# JediLightSwitch.net
KiCad netlist of a schematic drawn in EAGLE
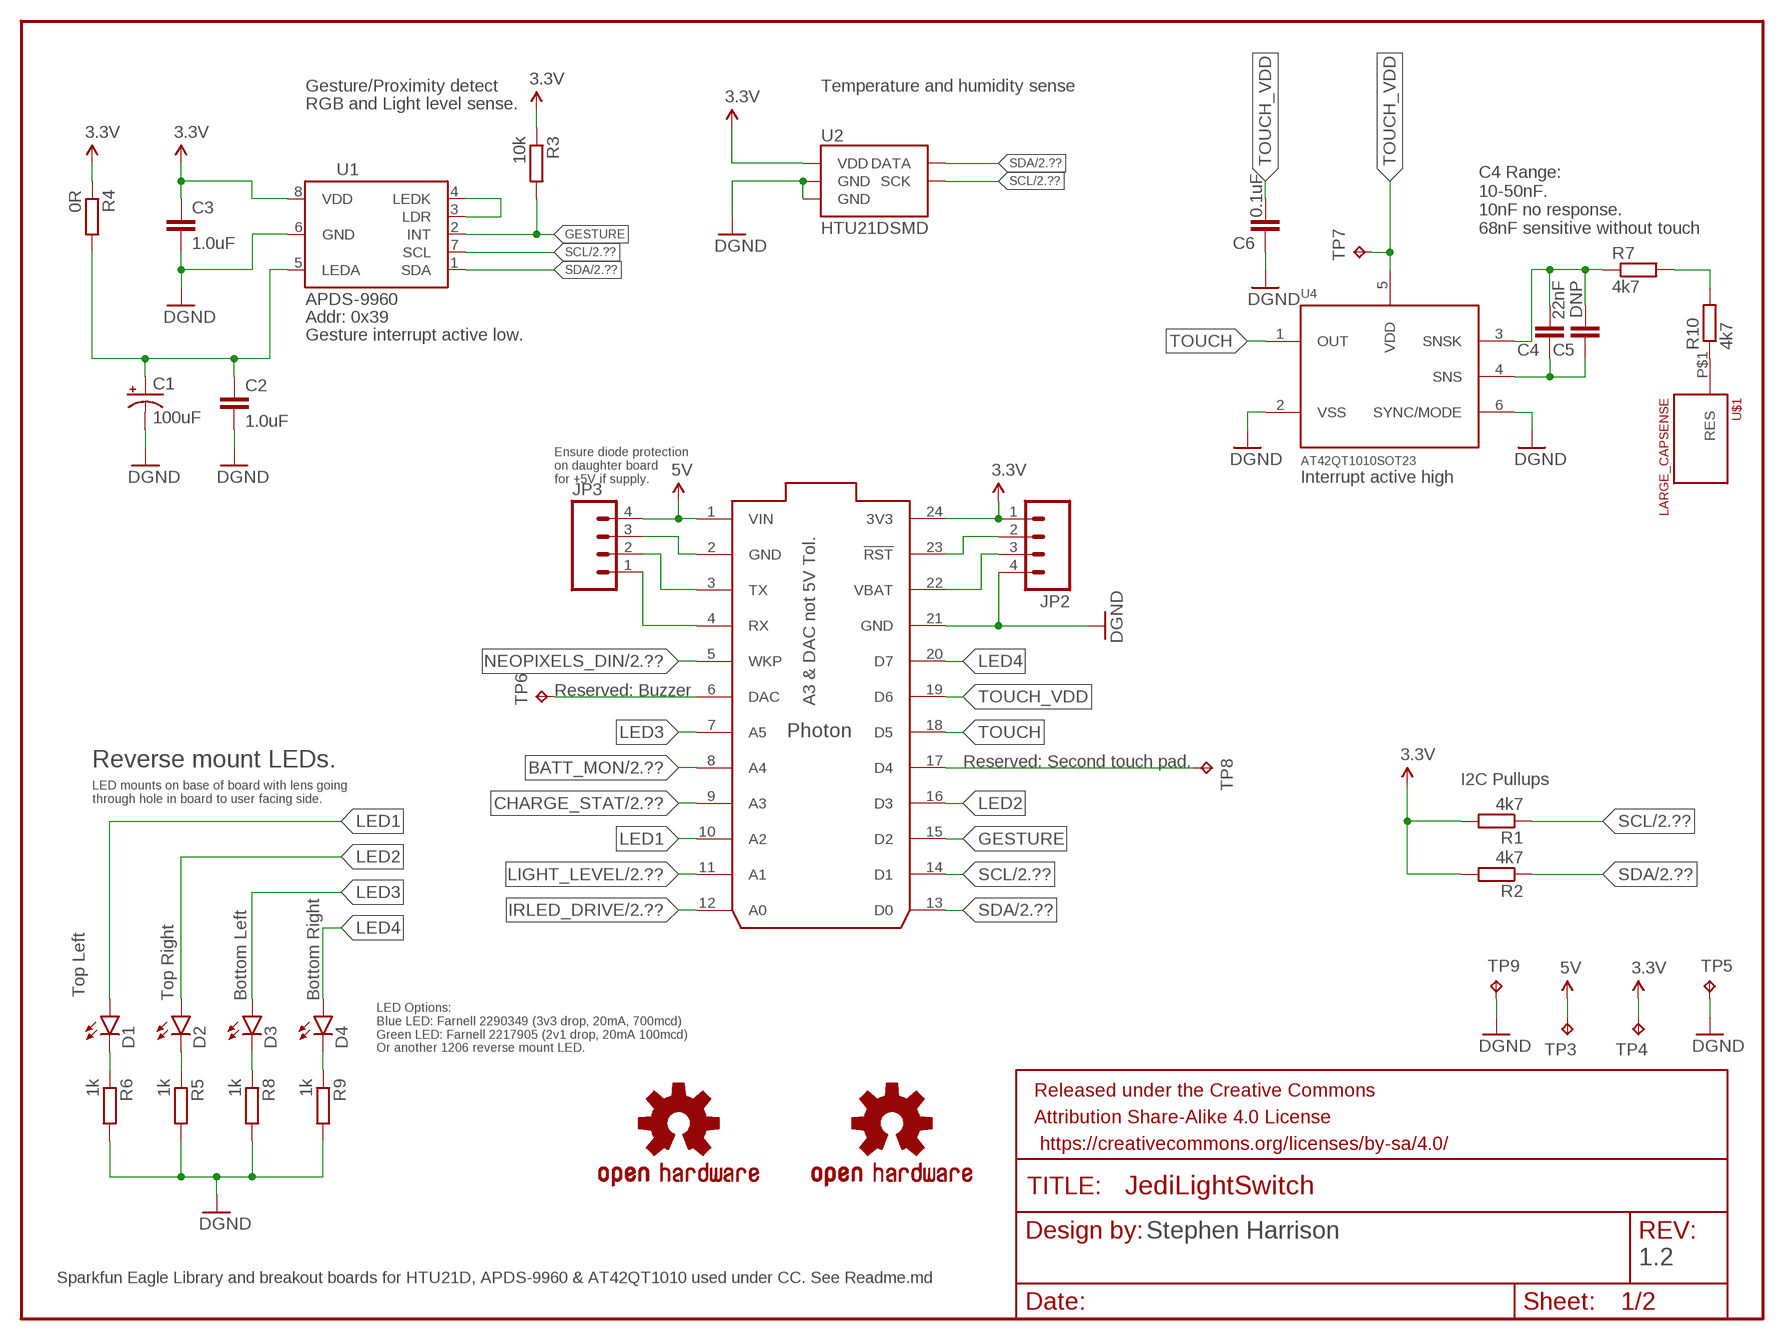
[diagram p0: schematic, sheet 1]
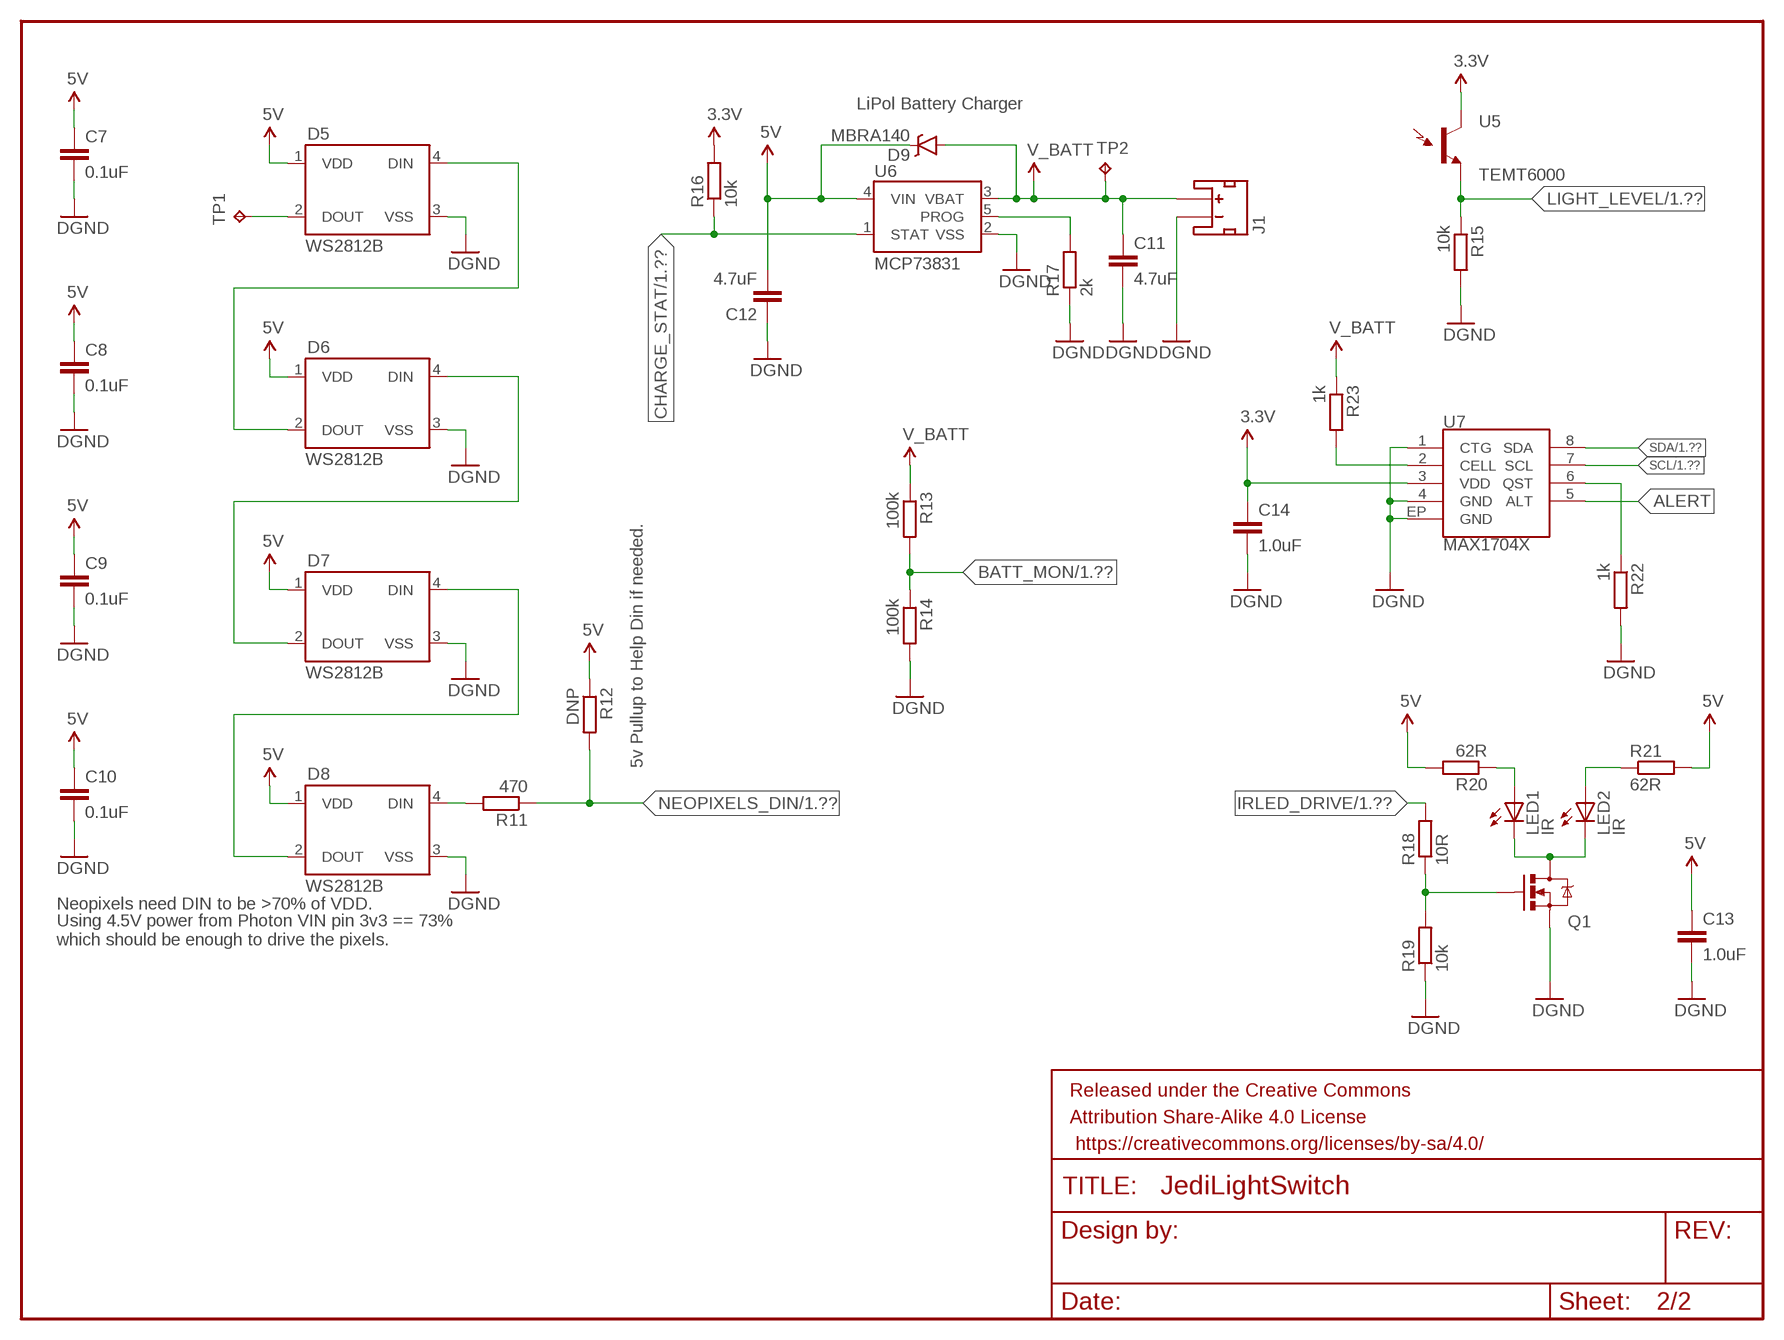
[diagram p1: schematic, sheet 2]

(export (version "E")
  (design (tool "Eeschema 10.0.6"))
  (components
    (comp (ref "C1")
      (value "100uF")
      (footprint "eagle-import:EIA7343")
      (libsource (lib "eagle-import") (part "100UF-10V-10%(TANT)"))
    )
    (comp (ref "C2")
      (value "1.0uF")
      (footprint "eagle-import:C0805")
      (libsource (lib "eagle-import") (part "C-EUC0805"))
    )
    (comp (ref "C3")
      (value "1.0uF")
      (footprint "eagle-import:C0805")
      (libsource (lib "eagle-import") (part "C-EUC0805"))
    )
    (comp (ref "C4")
      (value "22nF")
      (footprint "eagle-import:C0805")
      (libsource (lib "eagle-import") (part "C-EUC0805"))
    )
    (comp (ref "C5")
      (value "DNP")
      (footprint "eagle-import:C0805")
      (libsource (lib "eagle-import") (part "C-EUC0805"))
    )
    (comp (ref "C6")
      (value "0.1uF")
      (footprint "eagle-import:C0805")
      (libsource (lib "eagle-import") (part "C-EUC0805"))
    )
    (comp (ref "D1")
      (value "LED1206-BOTTOM")
      (footprint "eagle-import:LED-1206-BOTTOM")
      (libsource (lib "eagle-import") (part "LED1206-BOTTOM"))
    )
    (comp (ref "D2")
      (value "LED1206-BOTTOM")
      (footprint "eagle-import:LED-1206-BOTTOM")
      (libsource (lib "eagle-import") (part "LED1206-BOTTOM"))
    )
    (comp (ref "D3")
      (value "LED1206-BOTTOM")
      (footprint "eagle-import:LED-1206-BOTTOM")
      (libsource (lib "eagle-import") (part "LED1206-BOTTOM"))
    )
    (comp (ref "D4")
      (value "LED1206-BOTTOM")
      (footprint "eagle-import:LED-1206-BOTTOM")
      (libsource (lib "eagle-import") (part "LED1206-BOTTOM"))
    )
    (comp (ref "FRAME2")
      (value "FRAME-LETTER")
      (footprint "eagle-import:CREATIVE_COMMONS")
      (libsource (lib "eagle-import") (part "FRAME-LETTER"))
    )
    (comp (ref "JP2")
      (value "M04SMD_STRAIGHT_COMBO")
      (footprint "eagle-import:1X04_SMD_STRAIGHT_COMBO")
      (libsource (lib "eagle-import") (part "M04SMD_STRAIGHT_COMBO"))
    )
    (comp (ref "JP3")
      (value "M04SMD_STRAIGHT_COMBO")
      (footprint "eagle-import:1X04_SMD_STRAIGHT_COMBO")
      (libsource (lib "eagle-import") (part "M04SMD_STRAIGHT_COMBO"))
    )
    (comp (ref "LOGO1")
      (value "OSHW-LOGOM")
      (footprint "eagle-import:OSHW-LOGO-M")
      (libsource (lib "eagle-import") (part "OSHW-LOGOM"))
    )
    (comp (ref "LOGO2")
      (value "OSHW-LOGOM")
      (footprint "eagle-import:OSHW-LOGO-M")
      (libsource (lib "eagle-import") (part "OSHW-LOGOM"))
    )
    (comp (ref "R1")
      (value "4k7")
      (footprint "eagle-import:R0805")
      (libsource (lib "eagle-import") (part "R-EU_R0805"))
    )
    (comp (ref "R2")
      (value "4k7")
      (footprint "eagle-import:R0805")
      (libsource (lib "eagle-import") (part "R-EU_R0805"))
    )
    (comp (ref "R3")
      (value "10k")
      (footprint "eagle-import:R0805")
      (libsource (lib "eagle-import") (part "R-EU_R0805"))
    )
    (comp (ref "R4")
      (value "0R")
      (footprint "eagle-import:R0805")
      (libsource (lib "eagle-import") (part "R-EU_R0805"))
    )
    (comp (ref "R5")
      (value "1k")
      (footprint "eagle-import:R0805")
      (libsource (lib "eagle-import") (part "R-EU_R0805"))
    )
    (comp (ref "R6")
      (value "1k")
      (footprint "eagle-import:R0805")
      (libsource (lib "eagle-import") (part "R-EU_R0805"))
    )
    (comp (ref "R7")
      (value "4k7")
      (footprint "eagle-import:R0805")
      (libsource (lib "eagle-import") (part "R-EU_R0805"))
    )
    (comp (ref "R8")
      (value "1k")
      (footprint "eagle-import:R0805")
      (libsource (lib "eagle-import") (part "R-EU_R0805"))
    )
    (comp (ref "R9")
      (value "1k")
      (footprint "eagle-import:R0805")
      (libsource (lib "eagle-import") (part "R-EU_R0805"))
    )
    (comp (ref "R10")
      (value "4k7")
      (footprint "eagle-import:R0805")
      (libsource (lib "eagle-import") (part "R-EU_R0805"))
    )
    (comp (ref "TP3")
      (value "TPTP20R")
      (footprint "eagle-import:TP20R")
      (libsource (lib "eagle-import") (part "TPTP20R"))
    )
    (comp (ref "TP4")
      (value "3v3")
      (footprint "eagle-import:TP20R")
      (libsource (lib "eagle-import") (part "TPTP20R"))
    )
    (comp (ref "TP5")
      (value "TPTP20R")
      (footprint "eagle-import:TP20R")
      (libsource (lib "eagle-import") (part "TPTP20R"))
    )
    (comp (ref "TP6")
      (value "TPTP20R")
      (footprint "eagle-import:TP20R")
      (libsource (lib "eagle-import") (part "TPTP20R"))
    )
    (comp (ref "TP7")
      (value "TPTP20R")
      (footprint "eagle-import:TP20R")
      (libsource (lib "eagle-import") (part "TPTP20R"))
    )
    (comp (ref "TP8")
      (value "TPTP20R")
      (footprint "eagle-import:TP20R")
      (libsource (lib "eagle-import") (part "TPTP20R"))
    )
    (comp (ref "TP9")
      (value "TPTP20R")
      (footprint "eagle-import:TP20R")
      (libsource (lib "eagle-import") (part "TPTP20R"))
    )
    (comp (ref "U$1")
      (value "LARGE_CAPSENSE")
      (footprint "eagle-import:LARGE_CAPSENSE")
      (libsource (lib "eagle-import") (part "LARGE_CAPSENSE"))
    )
    (comp (ref "U1")
      (value "APDS-9960")
      (footprint "eagle-import:APDS-9960")
      (libsource (lib "eagle-import") (part "APDS-9960"))
    )
    (comp (ref "U2")
      (value "HTU21DSMD")
      (footprint "eagle-import:HTU21D")
      (libsource (lib "eagle-import") (part "HTU21DSMD"))
    )
    (comp (ref "U3")
      (value "PHOTON_SMD")
      (footprint "eagle-import:PHOTON_SMD")
      (libsource (lib "eagle-import") (part "PHOTON_SMD"))
    )
    (comp (ref "U4")
      (value "AT42QT1010SOT23")
      (footprint "eagle-import:SOT23-6")
      (libsource (lib "eagle-import") (part "AT42QT1010SOT23"))
    )
    (comp (ref "C7")
      (value "0.1uF")
      (footprint "eagle-import:C0805")
      (libsource (lib "eagle-import") (part "C-EUC0805"))
    )
    (comp (ref "C8")
      (value "0.1uF")
      (footprint "eagle-import:C0805")
      (libsource (lib "eagle-import") (part "C-EUC0805"))
    )
    (comp (ref "C9")
      (value "0.1uF")
      (footprint "eagle-import:C0805")
      (libsource (lib "eagle-import") (part "C-EUC0805"))
    )
    (comp (ref "C10")
      (value "0.1uF")
      (footprint "eagle-import:C0805")
      (libsource (lib "eagle-import") (part "C-EUC0805"))
    )
    (comp (ref "C11")
      (value "4.7uF")
      (footprint "eagle-import:C0805")
      (libsource (lib "eagle-import") (part "C-EUC0805"))
    )
    (comp (ref "C12")
      (value "4.7uF")
      (footprint "eagle-import:C0805")
      (libsource (lib "eagle-import") (part "C-EUC0805"))
    )
    (comp (ref "C13")
      (value "1.0uF")
      (footprint "eagle-import:C0805")
      (libsource (lib "eagle-import") (part "C-EUC0805"))
    )
    (comp (ref "C14")
      (value "1.0uF")
      (footprint "eagle-import:C0805")
      (libsource (lib "eagle-import") (part "C-EUC0805"))
    )
    (comp (ref "D5")
      (value "WS2812B")
      (footprint "eagle-import:WS2812B")
      (libsource (lib "eagle-import") (part "WS2812B"))
    )
    (comp (ref "D6")
      (value "WS2812B")
      (footprint "eagle-import:WS2812B")
      (libsource (lib "eagle-import") (part "WS2812B"))
    )
    (comp (ref "D7")
      (value "WS2812B")
      (footprint "eagle-import:WS2812B")
      (libsource (lib "eagle-import") (part "WS2812B"))
    )
    (comp (ref "D8")
      (value "WS2812B")
      (footprint "eagle-import:WS2812B")
      (libsource (lib "eagle-import") (part "WS2812B"))
    )
    (comp (ref "D9")
      (value "MBRA140")
      (footprint "eagle-import:SMA-DIODE")
      (libsource (lib "eagle-import") (part "MBRA140"))
    )
    (comp (ref "FRAME1")
      (value "FRAME-LETTERNO_PACKAGE")
      (footprint "eagle-import:DUMMY")
      (fields (field (name "DESIGNER") "Nobody"))
      (libsource (lib "eagle-import") (part "FRAME-LETTERNO_PACKAGE"))
    )
    (comp (ref "J1")
      (value "JST_2MM_MALE")
      (footprint "eagle-import:JST-2-SMD")
      (libsource (lib "eagle-import") (part "JST_2MM_MALE"))
    )
    (comp (ref "LED1")
      (value "IR")
      (footprint "eagle-import:1206")
      (libsource (lib "eagle-import") (part "LEDSMT1206"))
    )
    (comp (ref "LED2")
      (value "IR")
      (footprint "eagle-import:1206")
      (libsource (lib "eagle-import") (part "LEDSMT1206"))
    )
    (comp (ref "Q1")
      (value "MOSFET-NCHANNELAO3404A")
      (footprint "eagle-import:SOT23-3")
      (libsource (lib "eagle-import") (part "MOSFET-NCHANNELAO3404A"))
    )
    (comp (ref "R11")
      (value "470")
      (footprint "eagle-import:R0805")
      (libsource (lib "eagle-import") (part "R-EU_R0805"))
    )
    (comp (ref "R12")
      (value "DNP")
      (footprint "eagle-import:R0805")
      (libsource (lib "eagle-import") (part "R-EU_R0805"))
    )
    (comp (ref "R13")
      (value "100k")
      (footprint "eagle-import:R0805")
      (libsource (lib "eagle-import") (part "R-EU_R0805"))
    )
    (comp (ref "R14")
      (value "100k")
      (footprint "eagle-import:R0805")
      (libsource (lib "eagle-import") (part "R-EU_R0805"))
    )
    (comp (ref "R15")
      (value "10k")
      (footprint "eagle-import:R0805")
      (libsource (lib "eagle-import") (part "R-EU_R0805"))
    )
    (comp (ref "R16")
      (value "10k")
      (footprint "eagle-import:R0805")
      (libsource (lib "eagle-import") (part "R-EU_R0805"))
    )
    (comp (ref "R17")
      (value "2k")
      (footprint "eagle-import:R0805")
      (libsource (lib "eagle-import") (part "R-EU_R0805"))
    )
    (comp (ref "R18")
      (value "10R")
      (footprint "eagle-import:R0805")
      (libsource (lib "eagle-import") (part "R-EU_R0805"))
    )
    (comp (ref "R19")
      (value "10k")
      (footprint "eagle-import:R0805")
      (libsource (lib "eagle-import") (part "R-EU_R0805"))
    )
    (comp (ref "R20")
      (value "62R")
      (footprint "eagle-import:R0805")
      (libsource (lib "eagle-import") (part "R-EU_R0805"))
    )
    (comp (ref "R21")
      (value "62R")
      (footprint "eagle-import:R0805")
      (libsource (lib "eagle-import") (part "R-EU_R0805"))
    )
    (comp (ref "R22")
      (value "1k")
      (footprint "eagle-import:R0805")
      (libsource (lib "eagle-import") (part "R-EU_R0805"))
    )
    (comp (ref "R23")
      (value "1k")
      (footprint "eagle-import:R0805")
      (libsource (lib "eagle-import") (part "R-EU_R0805"))
    )
    (comp (ref "TP1")
      (value "TPTP20R")
      (footprint "eagle-import:TP20R")
      (libsource (lib "eagle-import") (part "TPTP20R"))
    )
    (comp (ref "TP2")
      (value "TPTP20R")
      (footprint "eagle-import:TP20R")
      (libsource (lib "eagle-import") (part "TPTP20R"))
    )
    (comp (ref "U5")
      (value "TEMT6000")
      (footprint "eagle-import:TEMT6000-SEN")
      (libsource (lib "eagle-import") (part "LIGHTSENSORTEMT6000"))
    )
    (comp (ref "U6")
      (value "MCP73831")
      (footprint "eagle-import:SOT23-5")
      (libsource (lib "eagle-import") (part "MCP73831"))
    )
    (comp (ref "U7")
      (value "MAX1704X")
      (footprint "eagle-import:TDFN-8")
      (libsource (lib "eagle-import") (part "MAX1704X"))
    )
  )
  (nets
    (net (code "1") (name "3.3V") (class "Default")
      (node (ref "C14") (pin "1") (pinfunction "1_1") (pintype "passive"))
      (node (ref "C3") (pin "1") (pinfunction "1_1") (pintype "passive"))
      (node (ref "JP2") (pin "1") (pinfunction "1_1") (pintype "passive"))
      (node (ref "R1") (pin "2") (pinfunction "2_2") (pintype "passive"))
      (node (ref "R16") (pin "2") (pinfunction "2_2") (pintype "passive"))
      (node (ref "R2") (pin "2") (pinfunction "2_2") (pintype "passive"))
      (node (ref "R3") (pin "1") (pinfunction "1_1") (pintype "passive"))
      (node (ref "R4") (pin "1") (pinfunction "1_1") (pintype "passive"))
      (node (ref "TP4") (pin "TP") (pinfunction "TP_TP") (pintype "input"))
      (node (ref "U1") (pin "8") (pinfunction "VDD_8") (pintype "bidirectional"))
      (node (ref "U2") (pin "VDD") (pinfunction "VDD_VDD") (pintype "power_in"))
      (node (ref "U3") (pin "24") (pinfunction "3V3_24") (pintype "power_in"))
      (node (ref "U5") (pin "COLLECTOR") (pinfunction "C1_COLLECTOR") (pintype "passive"))
      (node (ref "U7") (pin "3") (pinfunction "VDD_3") (pintype "bidirectional"))
    )
    (net (code "2") (name "5V") (class "Default")
      (node (ref "C10") (pin "1") (pinfunction "1_1") (pintype "passive"))
      (node (ref "C12") (pin "2") (pinfunction "2_2") (pintype "passive"))
      (node (ref "C13") (pin "1") (pinfunction "1_1") (pintype "passive"))
      (node (ref "C7") (pin "1") (pinfunction "1_1") (pintype "passive"))
      (node (ref "C8") (pin "1") (pinfunction "1_1") (pintype "passive"))
      (node (ref "C9") (pin "1") (pinfunction "1_1") (pintype "passive"))
      (node (ref "D5") (pin "1") (pinfunction "VDD_1") (pintype "power_in"))
      (node (ref "D6") (pin "1") (pinfunction "VDD_1") (pintype "power_in"))
      (node (ref "D7") (pin "1") (pinfunction "VDD_1") (pintype "power_in"))
      (node (ref "D8") (pin "1") (pinfunction "VDD_1") (pintype "power_in"))
      (node (ref "D9") (pin "C") (pinfunction "C_C") (pintype "passive"))
      (node (ref "JP3") (pin "4") (pinfunction "4_4") (pintype "passive"))
      (node (ref "R12") (pin "1") (pinfunction "1_1") (pintype "passive"))
      (node (ref "R20") (pin "2") (pinfunction "2_2") (pintype "passive"))
      (node (ref "R21") (pin "2") (pinfunction "2_2") (pintype "passive"))
      (node (ref "TP3") (pin "TP") (pinfunction "TP_TP") (pintype "input"))
      (node (ref "U3") (pin "1") (pinfunction "VIN_1") (pintype "power_in"))
      (node (ref "U6") (pin "4") (pinfunction "VIN_4") (pintype "power_in"))
    )
    (net (code "3") (name "ALERT") (class "Default")
      (node (ref "U7") (pin "5") (pinfunction "ALT_5") (pintype "bidirectional"))
    )
    (net (code "4") (name "BATT_MON") (class "Default")
      (node (ref "R13") (pin "2") (pinfunction "2_2") (pintype "passive"))
      (node (ref "R14") (pin "1") (pinfunction "1_1") (pintype "passive"))
      (node (ref "U3") (pin "8") (pinfunction "A4_8") (pintype "bidirectional"))
    )
    (net (code "5") (name "CHARGE_STAT") (class "Default")
      (node (ref "R16") (pin "1") (pinfunction "1_1") (pintype "passive"))
      (node (ref "U3") (pin "9") (pinfunction "A3_9") (pintype "bidirectional"))
      (node (ref "U6") (pin "1") (pinfunction "STAT_1") (pintype "output"))
    )
    (net (code "6") (name "GESTURE") (class "Default")
      (node (ref "R3") (pin "2") (pinfunction "2_2") (pintype "passive"))
      (node (ref "U1") (pin "2") (pinfunction "INT_2") (pintype "bidirectional"))
      (node (ref "U3") (pin "15") (pinfunction "D2_15") (pintype "bidirectional"))
    )
    (net (code "7") (name "GND") (class "Default")
      (node (ref "C1") (pin "C") (pinfunction "-_C") (pintype "passive"))
      (node (ref "C10") (pin "2") (pinfunction "2_2") (pintype "passive"))
      (node (ref "C11") (pin "2") (pinfunction "2_2") (pintype "passive"))
      (node (ref "C12") (pin "1") (pinfunction "1_1") (pintype "passive"))
      (node (ref "C13") (pin "2") (pinfunction "2_2") (pintype "passive"))
      (node (ref "C14") (pin "2") (pinfunction "2_2") (pintype "passive"))
      (node (ref "C2") (pin "2") (pinfunction "2_2") (pintype "passive"))
      (node (ref "C3") (pin "2") (pinfunction "2_2") (pintype "passive"))
      (node (ref "C6") (pin "1") (pinfunction "1_1") (pintype "passive"))
      (node (ref "C7") (pin "2") (pinfunction "2_2") (pintype "passive"))
      (node (ref "C8") (pin "2") (pinfunction "2_2") (pintype "passive"))
      (node (ref "C9") (pin "2") (pinfunction "2_2") (pintype "passive"))
      (node (ref "D5") (pin "3") (pinfunction "VSS_3") (pintype "power_in"))
      (node (ref "D6") (pin "3") (pinfunction "VSS_3") (pintype "power_in"))
      (node (ref "D7") (pin "3") (pinfunction "VSS_3") (pintype "power_in"))
      (node (ref "D8") (pin "3") (pinfunction "VSS_3") (pintype "power_in"))
      (node (ref "J1") (pin "1") (pinfunction "-_1") (pintype "bidirectional"))
      (node (ref "JP2") (pin "4") (pinfunction "4_4") (pintype "passive"))
      (node (ref "JP3") (pin "3") (pinfunction "3_3") (pintype "passive"))
      (node (ref "Q1") (pin "2") (pinfunction "S_2") (pintype "passive"))
      (node (ref "R14") (pin "2") (pinfunction "2_2") (pintype "passive"))
      (node (ref "R15") (pin "2") (pinfunction "2_2") (pintype "passive"))
      (node (ref "R17") (pin "1") (pinfunction "1_1") (pintype "passive"))
      (node (ref "R19") (pin "1") (pinfunction "1_1") (pintype "passive"))
      (node (ref "R22") (pin "2") (pinfunction "2_2") (pintype "passive"))
      (node (ref "R5") (pin "2") (pinfunction "2_2") (pintype "passive"))
      (node (ref "R6") (pin "2") (pinfunction "2_2") (pintype "passive"))
      (node (ref "R8") (pin "2") (pinfunction "2_2") (pintype "passive"))
      (node (ref "R9") (pin "2") (pinfunction "2_2") (pintype "passive"))
      (node (ref "TP5") (pin "TP") (pinfunction "TP_TP") (pintype "input"))
      (node (ref "TP9") (pin "TP") (pinfunction "TP_TP") (pintype "input"))
      (node (ref "U1") (pin "6") (pinfunction "GND_6") (pintype "bidirectional"))
      (node (ref "U2") (pin "7") (pinfunction "GND_7") (pintype "power_in"))
      (node (ref "U2") (pin "GND") (pinfunction "GND_GND") (pintype "power_in"))
      (node (ref "U3") (pin "2") (pinfunction "GND_2") (pintype "power_in"))
      (node (ref "U3") (pin "21") (pinfunction "GND_21") (pintype "power_in"))
      (node (ref "U4") (pin "2") (pinfunction "VSS_2") (pintype "bidirectional"))
      (node (ref "U4") (pin "6") (pinfunction "SYNC/MODE_6") (pintype "bidirectional"))
      (node (ref "U6") (pin "2") (pinfunction "VSS_2") (pintype "power_in"))
      (node (ref "U7") (pin "1") (pinfunction "CTG_1") (pintype "bidirectional"))
      (node (ref "U7") (pin "4") (pinfunction "GND_4") (pintype "bidirectional"))
      (node (ref "U7") (pin "EP") (pinfunction "GND_EP") (pintype "bidirectional"))
    )
    (net (code "8") (name "IRLED_DRIVE") (class "Default")
      (node (ref "R18") (pin "2") (pinfunction "2_2") (pintype "passive"))
      (node (ref "U3") (pin "12") (pinfunction "A0_12") (pintype "bidirectional"))
    )
    (net (code "9") (name "LED1") (class "Default")
      (node (ref "D1") (pin "A") (pinfunction "A_A") (pintype "passive"))
      (node (ref "U3") (pin "10") (pinfunction "A2_10") (pintype "bidirectional"))
    )
    (net (code "10") (name "LED2") (class "Default")
      (node (ref "D2") (pin "A") (pinfunction "A_A") (pintype "passive"))
      (node (ref "U3") (pin "16") (pinfunction "D3_16") (pintype "bidirectional"))
    )
    (net (code "11") (name "LED3") (class "Default")
      (node (ref "D3") (pin "A") (pinfunction "A_A") (pintype "passive"))
      (node (ref "U3") (pin "7") (pinfunction "A5_7") (pintype "bidirectional"))
    )
    (net (code "12") (name "LED4") (class "Default")
      (node (ref "D4") (pin "A") (pinfunction "A_A") (pintype "passive"))
      (node (ref "U3") (pin "20") (pinfunction "D7_20") (pintype "bidirectional"))
    )
    (net (code "13") (name "LIGHT_LEVEL") (class "Default")
      (node (ref "R15") (pin "1") (pinfunction "1_1") (pintype "passive"))
      (node (ref "U3") (pin "11") (pinfunction "A1_11") (pintype "bidirectional"))
      (node (ref "U5") (pin "EMITTER") (pinfunction "E1_EMITTER") (pintype "passive"))
    )
    (net (code "14") (name "NEOPIXELS_DIN") (class "Default")
      (node (ref "R11") (pin "1") (pinfunction "1_1") (pintype "passive"))
      (node (ref "R12") (pin "2") (pinfunction "2_2") (pintype "passive"))
      (node (ref "U3") (pin "5") (pinfunction "WKP_5") (pintype "bidirectional"))
    )
    (net (code "15") (name "Net-(C1-+)") (class "Default")
      (node (ref "C1") (pin "A") (pinfunction "+_A") (pintype "passive"))
      (node (ref "C2") (pin "1") (pinfunction "1_1") (pintype "passive"))
      (node (ref "R4") (pin "2") (pinfunction "2_2") (pintype "passive"))
      (node (ref "U1") (pin "5") (pinfunction "LEDA_5") (pintype "bidirectional"))
    )
    (net (code "16") (name "Net-(D1-PadC)") (class "Default")
      (node (ref "D1") (pin "C") (pinfunction "C_C") (pintype "passive"))
      (node (ref "R6") (pin "1") (pinfunction "1_1") (pintype "passive"))
    )
    (net (code "17") (name "Net-(D2-PadC)") (class "Default")
      (node (ref "D2") (pin "C") (pinfunction "C_C") (pintype "passive"))
      (node (ref "R5") (pin "1") (pinfunction "1_1") (pintype "passive"))
    )
    (net (code "18") (name "Net-(D3-PadC)") (class "Default")
      (node (ref "D3") (pin "C") (pinfunction "C_C") (pintype "passive"))
      (node (ref "R8") (pin "1") (pinfunction "1_1") (pintype "passive"))
    )
    (net (code "19") (name "Net-(D4-PadC)") (class "Default")
      (node (ref "D4") (pin "C") (pinfunction "C_C") (pintype "passive"))
      (node (ref "R9") (pin "1") (pinfunction "1_1") (pintype "passive"))
    )
    (net (code "20") (name "Net-(D5-DIN)") (class "Default")
      (node (ref "D5") (pin "4") (pinfunction "DIN_4") (pintype "input"))
      (node (ref "D6") (pin "2") (pinfunction "DOUT_2") (pintype "output"))
    )
    (net (code "21") (name "Net-(D5-DOUT)") (class "Default")
      (node (ref "D5") (pin "2") (pinfunction "DOUT_2") (pintype "output"))
      (node (ref "TP1") (pin "TP") (pinfunction "TP_TP") (pintype "input"))
    )
    (net (code "22") (name "Net-(D6-DIN)") (class "Default")
      (node (ref "D6") (pin "4") (pinfunction "DIN_4") (pintype "input"))
      (node (ref "D7") (pin "2") (pinfunction "DOUT_2") (pintype "output"))
    )
    (net (code "23") (name "Net-(D7-DIN)") (class "Default")
      (node (ref "D7") (pin "4") (pinfunction "DIN_4") (pintype "input"))
      (node (ref "D8") (pin "2") (pinfunction "DOUT_2") (pintype "output"))
    )
    (net (code "24") (name "Net-(D8-DIN)") (class "Default")
      (node (ref "D8") (pin "4") (pinfunction "DIN_4") (pintype "input"))
      (node (ref "R11") (pin "2") (pinfunction "2_2") (pintype "passive"))
    )
    (net (code "25") (name "Net-(LED1-PadA)") (class "Default")
      (node (ref "LED1") (pin "A") (pinfunction "A_A") (pintype "passive"))
      (node (ref "R20") (pin "1") (pinfunction "1_1") (pintype "passive"))
    )
    (net (code "26") (name "Net-(LED2-PadA)") (class "Default")
      (node (ref "LED2") (pin "A") (pinfunction "A_A") (pintype "passive"))
      (node (ref "R21") (pin "1") (pinfunction "1_1") (pintype "passive"))
    )
    (net (code "27") (name "Net-(Q1-D)") (class "Default")
      (node (ref "LED1") (pin "C") (pinfunction "C_C") (pintype "passive"))
      (node (ref "LED2") (pin "C") (pinfunction "C_C") (pintype "passive"))
      (node (ref "Q1") (pin "3") (pinfunction "D_3") (pintype "passive"))
    )
    (net (code "28") (name "Net-(Q1-G)") (class "Default")
      (node (ref "Q1") (pin "1") (pinfunction "G_1") (pintype "passive"))
      (node (ref "R18") (pin "1") (pinfunction "1_1") (pintype "passive"))
      (node (ref "R19") (pin "2") (pinfunction "2_2") (pintype "passive"))
    )
    (net (code "29") (name "Net-(R10-Pad2)") (class "Default")
      (node (ref "R10") (pin "2") (pinfunction "2_2") (pintype "passive"))
      (node (ref "R7") (pin "2") (pinfunction "2_2") (pintype "passive"))
    )
    (net (code "30") (name "Net-(U$1-RES)") (class "Default")
      (node (ref "R10") (pin "1") (pinfunction "1_1") (pintype "passive"))
      (node (ref "U$1") (pin "P$1") (pinfunction "RES_P$1") (pintype "bidirectional"))
    )
    (net (code "31") (name "Net-(U1-LDR)") (class "Default")
      (node (ref "U1") (pin "3") (pinfunction "LDR_3") (pintype "bidirectional"))
      (node (ref "U1") (pin "4") (pinfunction "LEDK_4") (pintype "bidirectional"))
    )
    (net (code "32") (name "Net-(U3A-D4)") (class "Default")
      (node (ref "TP8") (pin "TP") (pinfunction "TP_TP") (pintype "input"))
      (node (ref "U3") (pin "17") (pinfunction "D4_17") (pintype "bidirectional"))
    )
    (net (code "33") (name "Net-(U3A-DAC)") (class "Default")
      (node (ref "TP6") (pin "TP") (pinfunction "TP_TP") (pintype "input"))
      (node (ref "U3") (pin "6") (pinfunction "DAC_6") (pintype "bidirectional"))
    )
    (net (code "34") (name "Net-(U3A-RX)") (class "Default")
      (node (ref "JP3") (pin "1") (pinfunction "1_1") (pintype "passive"))
      (node (ref "U3") (pin "4") (pinfunction "RX_4") (pintype "bidirectional"))
    )
    (net (code "35") (name "Net-(U3A-TX)") (class "Default")
      (node (ref "JP3") (pin "2") (pinfunction "2_2") (pintype "passive"))
      (node (ref "U3") (pin "3") (pinfunction "TX_3") (pintype "bidirectional"))
    )
    (net (code "36") (name "Net-(U3A-VBAT)") (class "Default")
      (node (ref "JP2") (pin "3") (pinfunction "3_3") (pintype "passive"))
      (node (ref "U3") (pin "22") (pinfunction "VBAT_22") (pintype "power_in"))
    )
    (net (code "37") (name "Net-(U3A-~{RST})") (class "Default")
      (node (ref "JP2") (pin "2") (pinfunction "2_2") (pintype "passive"))
      (node (ref "U3") (pin "23") (pinfunction "~{RST}_23") (pintype "bidirectional"))
    )
    (net (code "38") (name "Net-(U4-SNS)") (class "Default")
      (node (ref "C4") (pin "1") (pinfunction "1_1") (pintype "passive"))
      (node (ref "C5") (pin "1") (pinfunction "1_1") (pintype "passive"))
      (node (ref "U4") (pin "4") (pinfunction "SNS_4") (pintype "bidirectional"))
    )
    (net (code "39") (name "Net-(U4-SNSK)") (class "Default")
      (node (ref "C4") (pin "2") (pinfunction "2_2") (pintype "passive"))
      (node (ref "C5") (pin "2") (pinfunction "2_2") (pintype "passive"))
      (node (ref "R7") (pin "1") (pinfunction "1_1") (pintype "passive"))
      (node (ref "U4") (pin "3") (pinfunction "SNSK_3") (pintype "bidirectional"))
    )
    (net (code "40") (name "Net-(U6-PROG)") (class "Default")
      (node (ref "R17") (pin "2") (pinfunction "2_2") (pintype "passive"))
      (node (ref "U6") (pin "5") (pinfunction "PROG_5") (pintype "input"))
    )
    (net (code "41") (name "Net-(U7-CELL)") (class "Default")
      (node (ref "R23") (pin "2") (pinfunction "2_2") (pintype "passive"))
      (node (ref "U7") (pin "2") (pinfunction "CELL_2") (pintype "bidirectional"))
    )
    (net (code "42") (name "Net-(U7-QST)") (class "Default")
      (node (ref "R22") (pin "1") (pinfunction "1_1") (pintype "passive"))
      (node (ref "U7") (pin "6") (pinfunction "QST_6") (pintype "bidirectional"))
    )
    (net (code "43") (name "SCL") (class "Default")
      (node (ref "R1") (pin "1") (pinfunction "1_1") (pintype "passive"))
      (node (ref "U1") (pin "7") (pinfunction "SCL_7") (pintype "bidirectional"))
      (node (ref "U2") (pin "SCK") (pinfunction "SCK_SCK") (pintype "input"))
      (node (ref "U3") (pin "14") (pinfunction "D1_14") (pintype "bidirectional"))
      (node (ref "U7") (pin "7") (pinfunction "SCL_7") (pintype "bidirectional"))
    )
    (net (code "44") (name "SDA") (class "Default")
      (node (ref "R2") (pin "1") (pinfunction "1_1") (pintype "passive"))
      (node (ref "U1") (pin "1") (pinfunction "SDA_1") (pintype "bidirectional"))
      (node (ref "U2") (pin "DATA") (pinfunction "DATA_DATA") (pintype "bidirectional"))
      (node (ref "U3") (pin "13") (pinfunction "D0_13") (pintype "bidirectional"))
      (node (ref "U7") (pin "8") (pinfunction "SDA_8") (pintype "bidirectional"))
    )
    (net (code "45") (name "TOUCH") (class "Default")
      (node (ref "U3") (pin "18") (pinfunction "D5_18") (pintype "bidirectional"))
      (node (ref "U4") (pin "1") (pinfunction "OUT_1") (pintype "bidirectional"))
    )
    (net (code "46") (name "TOUCH_VDD") (class "Default")
      (node (ref "C6") (pin "2") (pinfunction "2_2") (pintype "passive"))
      (node (ref "TP7") (pin "TP") (pinfunction "TP_TP") (pintype "input"))
      (node (ref "U3") (pin "19") (pinfunction "D6_19") (pintype "bidirectional"))
      (node (ref "U4") (pin "5") (pinfunction "VDD_5") (pintype "bidirectional"))
    )
    (net (code "47") (name "V_BATT") (class "Default")
      (node (ref "C11") (pin "1") (pinfunction "1_1") (pintype "passive"))
      (node (ref "D9") (pin "A") (pinfunction "A_A") (pintype "passive"))
      (node (ref "J1") (pin "2") (pinfunction "+_2") (pintype "bidirectional"))
      (node (ref "R13") (pin "1") (pinfunction "1_1") (pintype "passive"))
      (node (ref "R23") (pin "1") (pinfunction "1_1") (pintype "passive"))
      (node (ref "TP2") (pin "TP") (pinfunction "TP_TP") (pintype "input"))
      (node (ref "U6") (pin "3") (pinfunction "VBAT_3") (pintype "power_in"))
    )
    (net (code "48") (name "unconnected-(J1-PAD1-PadNC1)") (class "Default")
      (node (ref "J1") (pin "NC1") (pinfunction "PAD1_NC1") (pintype "bidirectional"))
    )
    (net (code "49") (name "unconnected-(J1-PAD2-PadNC2)") (class "Default")
      (node (ref "J1") (pin "NC2") (pinfunction "PAD2_NC2") (pintype "bidirectional"))
    )
  )
)
